# Motor.net
KiCad netlist of a schematic drawn in Altium Designer
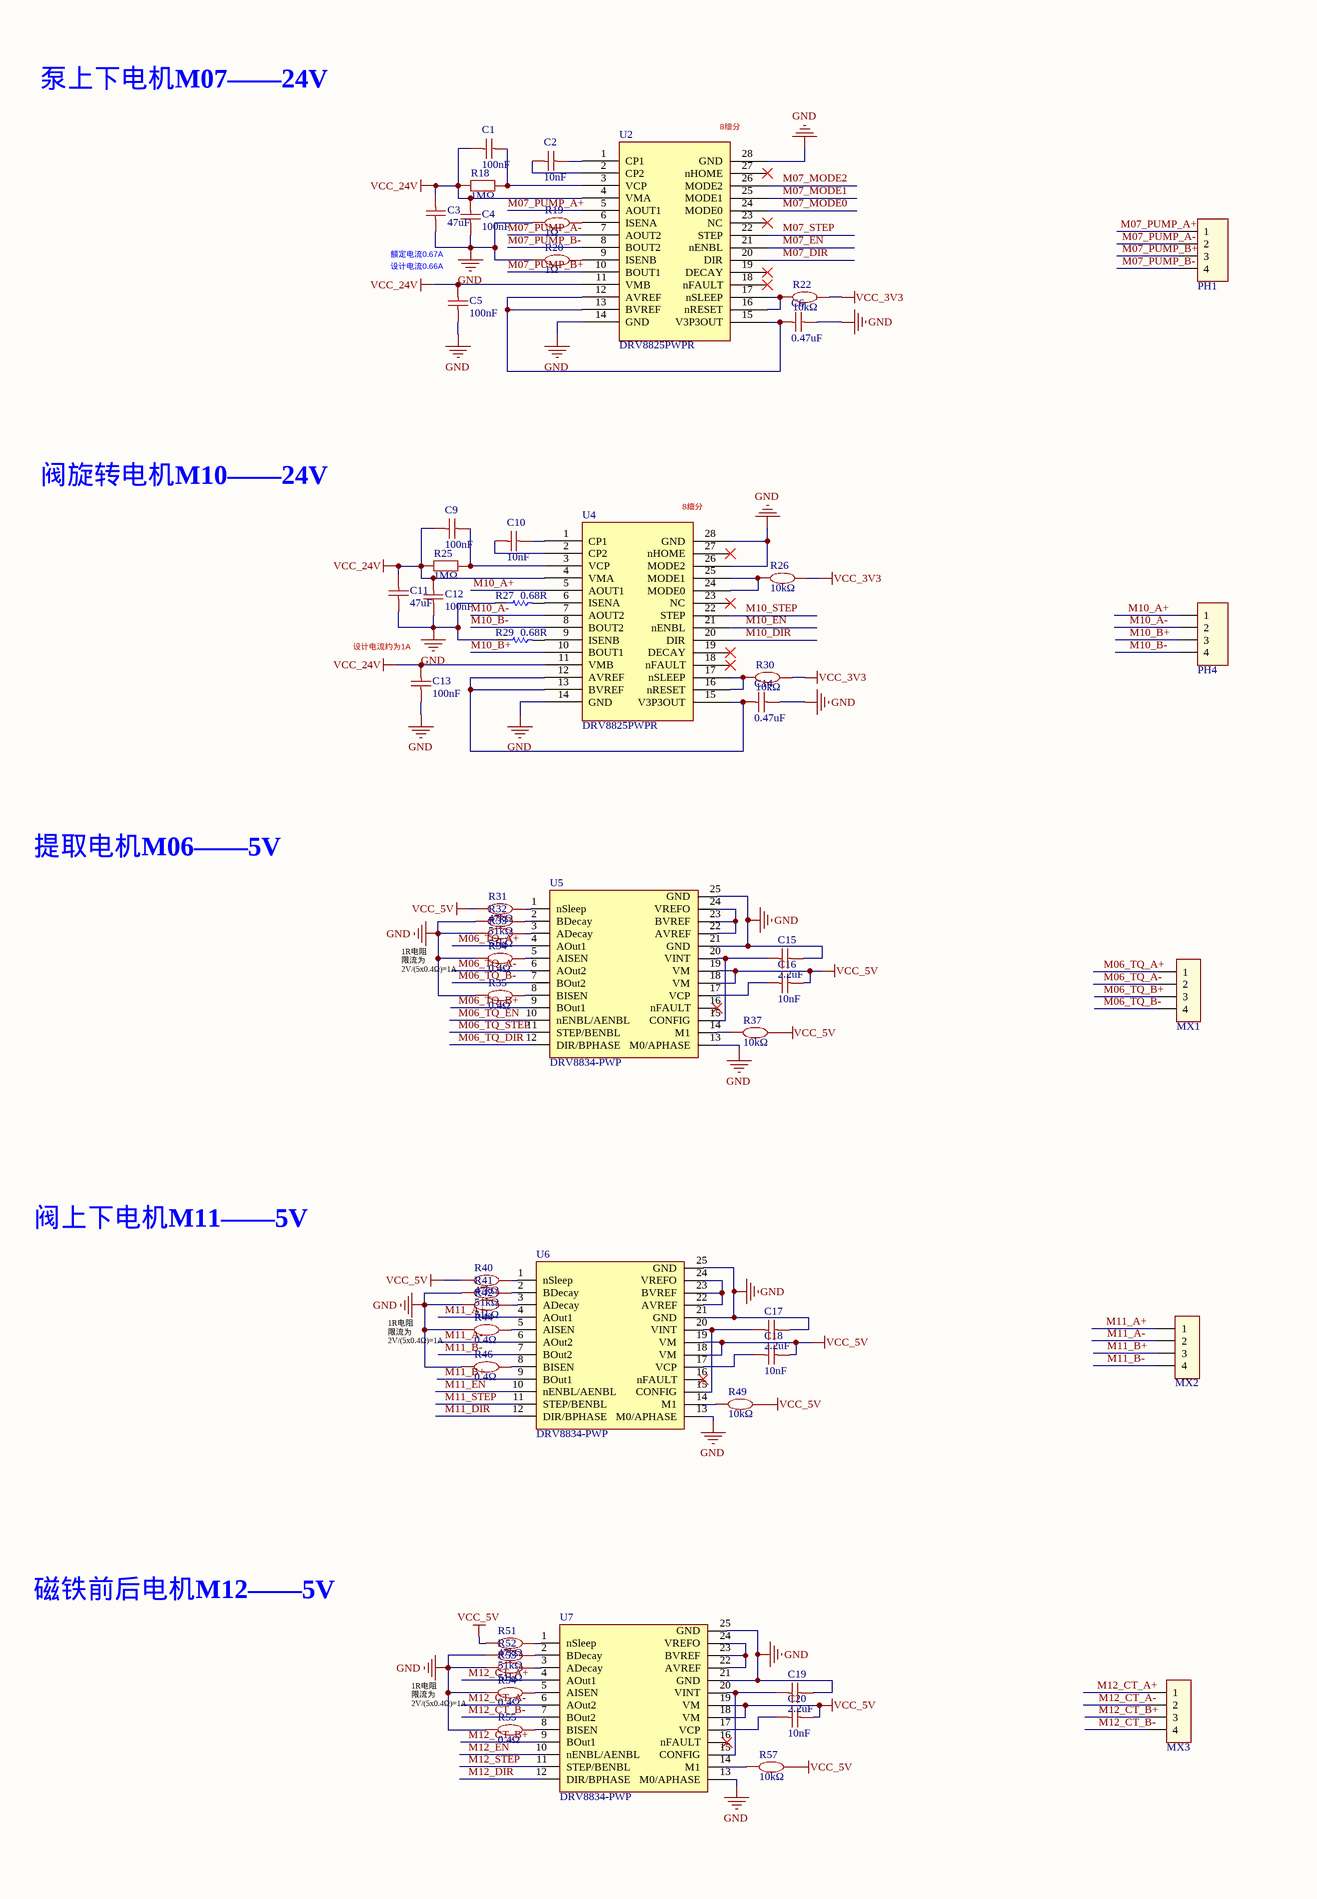
[diagram p0: Motor.SchDoc, left]
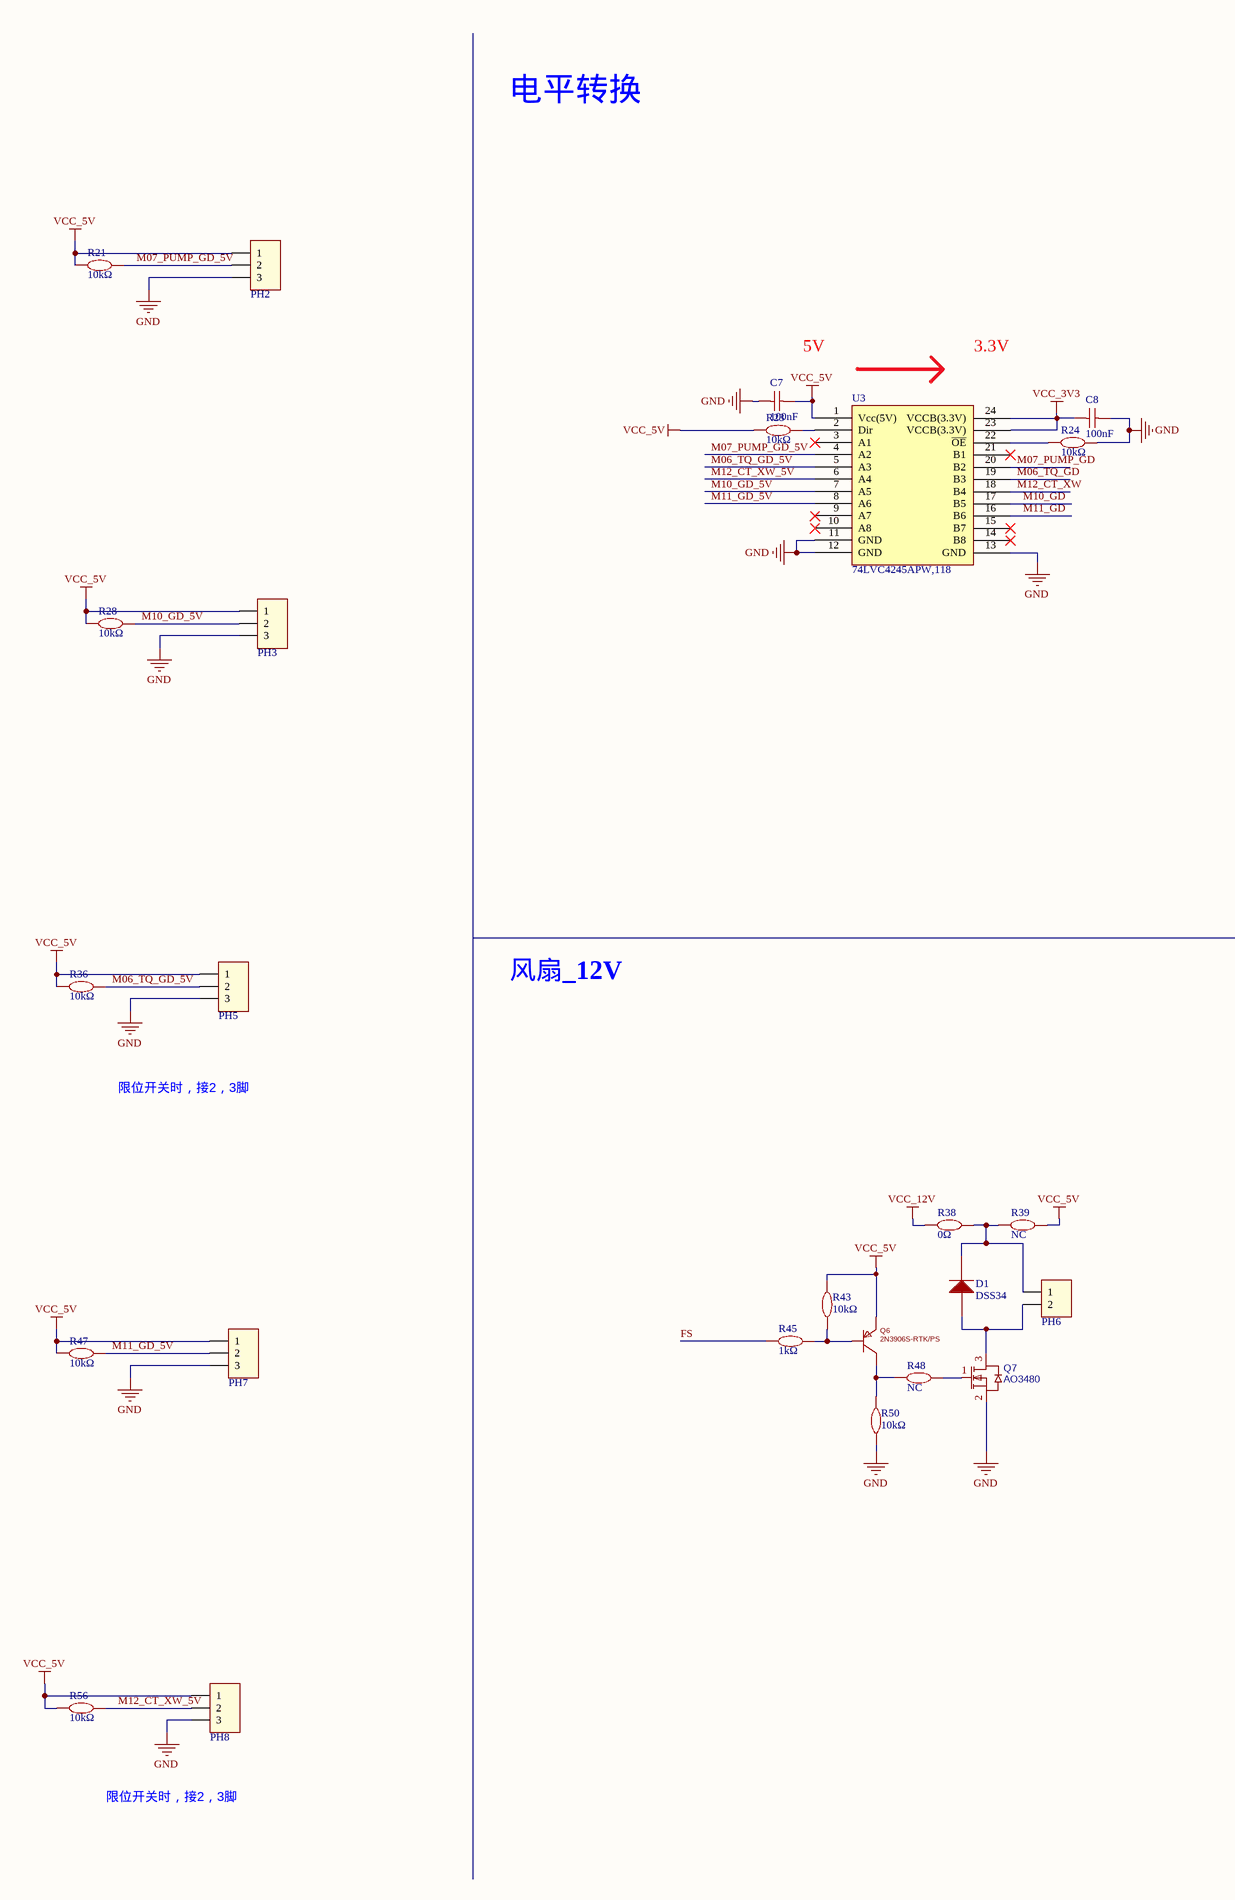
[diagram p1: Motor.SchDoc, right]

(export (version "E")
  (design (tool "Eeschema 10.0.6"))
  (components
    (comp (ref "C1")
      (value "100nF")
      (footprint "C0603")
      (description "贴片电容,X7R")
      (libsource (lib "XG_DW_POCT_2K10LED_3") (part "100nF/50V,C0603"))
    )
    (comp (ref "C2")
      (value "10nF")
      (footprint "C0603")
      (description "贴片电容,X7R")
      (libsource (lib "XG_DW_POCT_2K10LED_3") (part "10nF/50V,C0603"))
    )
    (comp (ref "C3")
      (value "47uF")
      (footprint "C1210")
      (description "贴片电容,X7R")
      (libsource (lib "XG_DW_POCT_2K10LED_3") (part "47uF/25V,C1210"))
    )
    (comp (ref "C4")
      (value "100nF")
      (footprint "C0603")
      (description "贴片电容,X7R")
      (libsource (lib "XG_DW_POCT_2K10LED_3") (part "100nF/50V,C0603"))
    )
    (comp (ref "C5")
      (value "100nF")
      (footprint "C0603")
      (description "贴片电容,X7R")
      (libsource (lib "XG_DW_POCT_2K10LED_3") (part "100nF/50V,C0603"))
    )
    (comp (ref "C6")
      (value "0.47uF")
      (footprint "C0603")
      (description "贴片电容,X7R")
      (libsource (lib "XG_DW_POCT_2K10LED_3") (part "0.47uF/50V,C0603"))
    )
    (comp (ref "C7")
      (value "100nF")
      (footprint "C0603")
      (description "贴片电容,X7R")
      (libsource (lib "XG_DW_POCT_2K10LED_3") (part "100nF/50V,C0603"))
    )
    (comp (ref "C8")
      (value "100nF")
      (footprint "C0603")
      (description "贴片电容,X7R")
      (libsource (lib "XG_DW_POCT_2K10LED_3") (part "100nF/50V,C0603"))
    )
    (comp (ref "C9")
      (value "100nF")
      (footprint "C0603")
      (description "贴片电容,X7R")
      (libsource (lib "XG_DW_POCT_2K10LED_3") (part "100nF/50V,C0603"))
    )
    (comp (ref "C10")
      (value "10nF")
      (footprint "C0603")
      (description "贴片电容,X7R")
      (libsource (lib "XG_DW_POCT_2K10LED_3") (part "10nF/50V,C0603"))
    )
    (comp (ref "C11")
      (value "47uF")
      (footprint "C1210")
      (description "贴片电容,X7R")
      (libsource (lib "XG_DW_POCT_2K10LED_3") (part "47uF/25V,C1210"))
    )
    (comp (ref "C12")
      (value "100nF")
      (footprint "C0603")
      (description "贴片电容,X7R")
      (libsource (lib "XG_DW_POCT_2K10LED_3") (part "100nF/50V,C0603"))
    )
    (comp (ref "C13")
      (value "100nF")
      (footprint "C0603")
      (description "贴片电容,X7R")
      (libsource (lib "XG_DW_POCT_2K10LED_3") (part "100nF/50V,C0603"))
    )
    (comp (ref "C14")
      (value "0.47uF")
      (footprint "C0603")
      (description "贴片电容,X7R")
      (libsource (lib "XG_DW_POCT_2K10LED_3") (part "0.47uF/50V,C0603"))
    )
    (comp (ref "C15")
      (value "2.2uF")
      (footprint "C0603")
      (description "贴片电容,X7R")
      (libsource (lib "XG_DW_POCT_2K10LED_3") (part "2.2uF/50V,C0603"))
    )
    (comp (ref "C16")
      (value "10nF")
      (footprint "C0603")
      (description "贴片电容,X7R")
      (libsource (lib "XG_DW_POCT_2K10LED_3") (part "10nF/50V,C0603"))
    )
    (comp (ref "C17")
      (value "2.2uF")
      (footprint "C0603")
      (description "贴片电容,X7R")
      (libsource (lib "XG_DW_POCT_2K10LED_3") (part "2.2uF/50V,C0603"))
    )
    (comp (ref "C18")
      (value "10nF")
      (footprint "C0603")
      (description "贴片电容,X7R")
      (libsource (lib "XG_DW_POCT_2K10LED_3") (part "10nF/50V,C0603"))
    )
    (comp (ref "C19")
      (value "2.2uF")
      (footprint "C0603")
      (description "贴片电容,X7R")
      (libsource (lib "XG_DW_POCT_2K10LED_3") (part "2.2uF/50V,C0603"))
    )
    (comp (ref "C20")
      (value "10nF")
      (footprint "C0603")
      (description "贴片电容,X7R")
      (libsource (lib "XG_DW_POCT_2K10LED_3") (part "10nF/50V,C0603"))
    )
    (comp (ref "D1")
      (value "DSS34")
      (footprint "SOD-123")
      (description "肖特基二极管")
      (libsource (lib "XG_DW_POCT_2K10LED_3") (part "DSS34,SOD-123"))
    )
    (comp (ref "MX1")
      (value "MX1.25-4P")
      (footprint "CONN-TH_4P-P1.25_HCTL_HC-1.25-4AW")
      (libsource (lib "XG_DW_POCT_2K10LED_3") (part "MX1.25-4P"))
    )
    (comp (ref "MX2")
      (value "MX1.25-4P")
      (footprint "CONN-TH_4P-P1.25_HCTL_HC-1.25-4AW")
      (libsource (lib "XG_DW_POCT_2K10LED_3") (part "MX1.25-4P"))
    )
    (comp (ref "MX3")
      (value "MX1.25-4P")
      (footprint "CONN-TH_4P-P1.25_HCTL_HC-1.25-4AW")
      (libsource (lib "XG_DW_POCT_2K10LED_3") (part "MX1.25-4P"))
    )
    (comp (ref "PH1")
      (value "PH2.0-4P")
      (footprint "PH2.0-4P 弯针")
      (libsource (lib "XG_DW_POCT_2K10LED_3") (part "PH2.0-4P"))
    )
    (comp (ref "PH2")
      (value "PH2.0-3P")
      (footprint "PH2.0-3P 弯针")
      (libsource (lib "XG_DW_POCT_2K10LED_3") (part "PH2.0-3P"))
    )
    (comp (ref "PH3")
      (value "PH2.0-3P")
      (footprint "PH2.0-3P 弯针")
      (libsource (lib "XG_DW_POCT_2K10LED_3") (part "PH2.0-3P"))
    )
    (comp (ref "PH4")
      (value "PH2.0-4P")
      (footprint "PH2.0-4P 弯针")
      (libsource (lib "XG_DW_POCT_2K10LED_3") (part "PH2.0-4P"))
    )
    (comp (ref "PH5")
      (value "PH2.0-3P")
      (footprint "PH2.0-3P 弯针")
      (libsource (lib "XG_DW_POCT_2K10LED_3") (part "PH2.0-3P"))
    )
    (comp (ref "PH6")
      (value "PH2.0-2P")
      (footprint "PH2.0-2P 弯针")
      (libsource (lib "XG_DW_POCT_2K10LED_3") (part "PH2.0-2P"))
    )
    (comp (ref "PH7")
      (value "PH2.0-3P")
      (footprint "PH2.0-3P 弯针")
      (libsource (lib "XG_DW_POCT_2K10LED_3") (part "PH2.0-3P"))
    )
    (comp (ref "PH8")
      (value "PH2.0-3P")
      (footprint "PH2.0-3P 弯针")
      (libsource (lib "XG_DW_POCT_2K10LED_3") (part "PH2.0-3P"))
    )
    (comp (ref "Q6")
      (value "2N3906S-RTK/PS")
      (footprint "SOT-23-3_L2.9-W1.3-P1.90-LS2.4-TR")
      (fields (field (name "MANUFACTURER") "KEC"))
      (libsource (lib "XG_DW_POCT_2K10LED_3") (part "2N3906S-RTK/PS"))
    )
    (comp (ref "Q7")
      (value "AO3480")
      (footprint "SOT-23(SOT-23-3)")
      (libsource (lib "XG_DW_POCT_2K10LED_3") (part "AO3480"))
    )
    (comp (ref "R18")
      (value "1MΩ")
      (footprint "R0603")
      (description "贴片电阻")
      (libsource (lib "XG_DW_POCT_2K10LED_3") (part "1MΩ,R0603"))
    )
    (comp (ref "R19")
      (value "1Ω")
      (footprint "R0603")
      (description "贴片电阻")
      (libsource (lib "XG_DW_POCT_2K10LED_3") (part "1Ω,R0603"))
    )
    (comp (ref "R20")
      (value "1Ω")
      (footprint "R0603")
      (description "贴片电阻")
      (libsource (lib "XG_DW_POCT_2K10LED_3") (part "1Ω,R0603"))
    )
    (comp (ref "R21")
      (value "10kΩ")
      (footprint "R0603")
      (description "电阻类型:厚膜电阻;阻值:10kΩ;精度:±1%;功率:100mW;最大工作电压:75V;温度系数:±100ppm/℃;")
      (libsource (lib "XG_DW_POCT_2K10LED_3") (part "10kΩ,R0603"))
    )
    (comp (ref "R22")
      (value "10kΩ")
      (footprint "R0603")
      (description "电阻类型:厚膜电阻;阻值:10kΩ;精度:±1%;功率:100mW;最大工作电压:75V;温度系数:±100ppm/℃;")
      (libsource (lib "XG_DW_POCT_2K10LED_3") (part "10kΩ,R0603"))
    )
    (comp (ref "R23")
      (value "10kΩ")
      (footprint "R0603")
      (description "电阻类型:厚膜电阻;阻值:10kΩ;精度:±1%;功率:100mW;最大工作电压:75V;温度系数:±100ppm/℃;")
      (libsource (lib "XG_DW_POCT_2K10LED_3") (part "10kΩ,R0603"))
    )
    (comp (ref "R24")
      (value "10kΩ")
      (footprint "R0603")
      (description "电阻类型:厚膜电阻;阻值:10kΩ;精度:±1%;功率:100mW;最大工作电压:75V;温度系数:±100ppm/℃;")
      (libsource (lib "XG_DW_POCT_2K10LED_3") (part "10kΩ,R0603"))
    )
    (comp (ref "R25")
      (value "1MΩ")
      (footprint "R0603")
      (description "贴片电阻")
      (libsource (lib "XG_DW_POCT_2K10LED_3") (part "1MΩ,R0603"))
    )
    (comp (ref "R26")
      (value "10kΩ")
      (footprint "R0603")
      (description "电阻类型:厚膜电阻;阻值:10kΩ;精度:±1%;功率:100mW;最大工作电压:75V;温度系数:±100ppm/℃;")
      (libsource (lib "XG_DW_POCT_2K10LED_3") (part "10kΩ,R0603"))
    )
    (comp (ref "R27")
      (value "0.68R")
      (footprint "R0603")
      (description "Resistor")
      (fields (field (name "PUBLISHER") "Altium Limited"))
      (libsource (lib "czb") (part "Res"))
    )
    (comp (ref "R28")
      (value "10kΩ")
      (footprint "R0603")
      (description "电阻类型:厚膜电阻;阻值:10kΩ;精度:±1%;功率:100mW;最大工作电压:75V;温度系数:±100ppm/℃;")
      (libsource (lib "XG_DW_POCT_2K10LED_3") (part "10kΩ,R0603"))
    )
    (comp (ref "R29")
      (value "0.68R")
      (footprint "R0603")
      (description "Resistor")
      (fields (field (name "PUBLISHER") "Altium Limited"))
      (libsource (lib "czb") (part "Res"))
    )
    (comp (ref "R30")
      (value "10kΩ")
      (footprint "R0603")
      (description "电阻类型:厚膜电阻;阻值:10kΩ;精度:±1%;功率:100mW;最大工作电压:75V;温度系数:±100ppm/℃;")
      (libsource (lib "XG_DW_POCT_2K10LED_3") (part "10kΩ,R0603"))
    )
    (comp (ref "R31")
      (value "47kΩ")
      (footprint "R0603")
      (description "贴片电阻")
      (libsource (lib "XG_DW_POCT_2K10LED_3") (part "47kΩ,R0603"))
    )
    (comp (ref "R32")
      (value "51kΩ")
      (footprint "R0603")
      (description "电阻类型:厚膜电阻;阻值:51kΩ;精度:±1%;功率:100mW;最大工作电压:75V;温度系数:±100ppm/℃;")
      (libsource (lib "XG_DW_POCT_2K10LED_3") (part "51kΩ,R0603"))
    )
    (comp (ref "R33")
      (value "51kΩ")
      (footprint "R0603")
      (description "电阻类型:厚膜电阻;阻值:51kΩ;精度:±1%;功率:100mW;最大工作电压:75V;温度系数:±100ppm/℃;")
      (libsource (lib "XG_DW_POCT_2K10LED_3") (part "51kΩ,R0603"))
    )
    (comp (ref "R34")
      (value "0.4Ω")
      (footprint "R0603")
      (description "贴片电阻")
      (libsource (lib "XG_DW_POCT_2K10LED_3") (part "0.4Ω,R0603"))
    )
    (comp (ref "R35")
      (value "0.4Ω")
      (footprint "R0603")
      (description "贴片电阻")
      (libsource (lib "XG_DW_POCT_2K10LED_3") (part "0.4Ω,R0603"))
    )
    (comp (ref "R36")
      (value "10kΩ")
      (footprint "R0603")
      (description "电阻类型:厚膜电阻;阻值:10kΩ;精度:±1%;功率:100mW;最大工作电压:75V;温度系数:±100ppm/℃;")
      (libsource (lib "XG_DW_POCT_2K10LED_3") (part "10kΩ,R0603"))
    )
    (comp (ref "R37")
      (value "10kΩ")
      (footprint "R0603")
      (description "电阻类型:厚膜电阻;阻值:10kΩ;精度:±1%;功率:100mW;最大工作电压:75V;温度系数:±100ppm/℃;")
      (libsource (lib "XG_DW_POCT_2K10LED_3") (part "10kΩ,R0603"))
    )
    (comp (ref "R38")
      (value "0Ω")
      (footprint "R0603")
      (description "贴片电阻")
      (libsource (lib "XG_DW_POCT_2K10LED_3") (part "0Ω,R0603"))
    )
    (comp (ref "R39")
      (value "NC")
      (footprint "R0603")
      (libsource (lib "XG_DW_POCT_2K10LED_3") (part "NC,R0603"))
    )
    (comp (ref "R40")
      (value "47kΩ")
      (footprint "R0603")
      (description "贴片电阻")
      (libsource (lib "XG_DW_POCT_2K10LED_3") (part "47kΩ,R0603"))
    )
    (comp (ref "R41")
      (value "51kΩ")
      (footprint "R0603")
      (description "电阻类型:厚膜电阻;阻值:51kΩ;精度:±1%;功率:100mW;最大工作电压:75V;温度系数:±100ppm/℃;")
      (libsource (lib "XG_DW_POCT_2K10LED_3") (part "51kΩ,R0603"))
    )
    (comp (ref "R42")
      (value "51kΩ")
      (footprint "R0603")
      (description "电阻类型:厚膜电阻;阻值:51kΩ;精度:±1%;功率:100mW;最大工作电压:75V;温度系数:±100ppm/℃;")
      (libsource (lib "XG_DW_POCT_2K10LED_3") (part "51kΩ,R0603"))
    )
    (comp (ref "R43")
      (value "10kΩ")
      (footprint "R0603")
      (description "电阻类型:厚膜电阻;阻值:10kΩ;精度:±1%;功率:100mW;最大工作电压:75V;温度系数:±100ppm/℃;")
      (libsource (lib "XG_DW_POCT_2K10LED_3") (part "10kΩ,R0603"))
    )
    (comp (ref "R44")
      (value "0.4Ω")
      (footprint "R0603")
      (description "贴片电阻")
      (libsource (lib "XG_DW_POCT_2K10LED_3") (part "0.4Ω,R0603"))
    )
    (comp (ref "R45")
      (value "1kΩ")
      (footprint "R0603")
      (description "电阻类型:厚膜电阻;阻值:1kΩ;精度:±1%;功率:125mW;最大工作电压:150V;温度系数:±100ppm/℃;")
      (libsource (lib "XG_DW_POCT_2K10LED_3") (part "1kΩ,R0603"))
    )
    (comp (ref "R46")
      (value "0.4Ω")
      (footprint "R0603")
      (description "贴片电阻")
      (libsource (lib "XG_DW_POCT_2K10LED_3") (part "0.4Ω,R0603"))
    )
    (comp (ref "R47")
      (value "10kΩ")
      (footprint "R0603")
      (description "电阻类型:厚膜电阻;阻值:10kΩ;精度:±1%;功率:100mW;最大工作电压:75V;温度系数:±100ppm/℃;")
      (libsource (lib "XG_DW_POCT_2K10LED_3") (part "10kΩ,R0603"))
    )
    (comp (ref "R48")
      (value "NC")
      (footprint "R0603")
      (libsource (lib "XG_DW_POCT_2K10LED_3") (part "NC,R0603"))
    )
    (comp (ref "R49")
      (value "10kΩ")
      (footprint "R0603")
      (description "电阻类型:厚膜电阻;阻值:10kΩ;精度:±1%;功率:100mW;最大工作电压:75V;温度系数:±100ppm/℃;")
      (libsource (lib "XG_DW_POCT_2K10LED_3") (part "10kΩ,R0603"))
    )
    (comp (ref "R50")
      (value "10kΩ")
      (footprint "R0603")
      (description "电阻类型:厚膜电阻;阻值:10kΩ;精度:±1%;功率:100mW;最大工作电压:75V;温度系数:±100ppm/℃;")
      (libsource (lib "XG_DW_POCT_2K10LED_3") (part "10kΩ,R0603"))
    )
    (comp (ref "R51")
      (value "47kΩ")
      (footprint "R0603")
      (description "贴片电阻")
      (libsource (lib "XG_DW_POCT_2K10LED_3") (part "47kΩ,R0603"))
    )
    (comp (ref "R52")
      (value "51kΩ")
      (footprint "R0603")
      (description "电阻类型:厚膜电阻;阻值:51kΩ;精度:±1%;功率:100mW;最大工作电压:75V;温度系数:±100ppm/℃;")
      (libsource (lib "XG_DW_POCT_2K10LED_3") (part "51kΩ,R0603"))
    )
    (comp (ref "R53")
      (value "51kΩ")
      (footprint "R0603")
      (description "电阻类型:厚膜电阻;阻值:51kΩ;精度:±1%;功率:100mW;最大工作电压:75V;温度系数:±100ppm/℃;")
      (libsource (lib "XG_DW_POCT_2K10LED_3") (part "51kΩ,R0603"))
    )
    (comp (ref "R54")
      (value "0.4Ω")
      (footprint "R0603")
      (description "贴片电阻")
      (libsource (lib "XG_DW_POCT_2K10LED_3") (part "0.4Ω,R0603"))
    )
    (comp (ref "R55")
      (value "0.4Ω")
      (footprint "R0603")
      (description "贴片电阻")
      (libsource (lib "XG_DW_POCT_2K10LED_3") (part "0.4Ω,R0603"))
    )
    (comp (ref "R56")
      (value "10kΩ")
      (footprint "R0603")
      (description "电阻类型:厚膜电阻;阻值:10kΩ;精度:±1%;功率:100mW;最大工作电压:75V;温度系数:±100ppm/℃;")
      (libsource (lib "XG_DW_POCT_2K10LED_3") (part "10kΩ,R0603"))
    )
    (comp (ref "R57")
      (value "10kΩ")
      (footprint "R0603")
      (description "电阻类型:厚膜电阻;阻值:10kΩ;精度:±1%;功率:100mW;最大工作电压:75V;温度系数:±100ppm/℃;")
      (libsource (lib "XG_DW_POCT_2K10LED_3") (part "10kΩ,R0603"))
    )
    (comp (ref "U2")
      (value "DRV8825PWPR")
      (footprint "HTSSOP-28")
      (libsource (lib "XG_DW_POCT_2K10LED_3") (part "DRV8825PWPR"))
    )
    (comp (ref "U3")
      (value "74LVC4245APW,118")
      (footprint "TSSOP-24")
      (description "转换器/电平移位器；通道类型 双向；工作电压(VCCA) 1.5V~5.5V；工作电压(VCCB) 1.5V~3.6V； 通道数 1；\r\n每个电路通道数 8；输出类型 三态")
      (libsource (lib "XG_DW_POCT_2K10LED_3") (part "74LVC4245APW"))
    )
    (comp (ref "U4")
      (value "DRV8825PWPR")
      (footprint "HTSSOP-28")
      (libsource (lib "XG_DW_POCT_2K10LED_3") (part "DRV8825PWPR"))
    )
    (comp (ref "U5")
      (value "DRV8834-PWP")
      (footprint "HTSSOP-24")
      (libsource (lib "XG_DW_POCT_2K10LED_3") (part "DRV8834-PWP"))
    )
    (comp (ref "U6")
      (value "DRV8834-PWP")
      (footprint "HTSSOP-24")
      (libsource (lib "XG_DW_POCT_2K10LED_3") (part "DRV8834-PWP"))
    )
    (comp (ref "U7")
      (value "DRV8834-PWP")
      (footprint "HTSSOP-24")
      (libsource (lib "XG_DW_POCT_2K10LED_3") (part "DRV8834-PWP"))
    )
  )
  (nets
    (net (code "1") (name "/FS") (class "Default")
      (node (ref "R45") (pin "2") (pinfunction "2_2") (pintype "passive"))
    )
    (net (code "2") (name "/M06_TQ_A+") (class "Default")
      (node (ref "MX1") (pin "1") (pinfunction "1_1") (pintype "passive"))
      (node (ref "U5") (pin "4") (pinfunction "AOut1_4") (pintype "passive"))
    )
    (net (code "3") (name "/M06_TQ_A-") (class "Default")
      (node (ref "MX1") (pin "2") (pinfunction "2_2") (pintype "passive"))
      (node (ref "U5") (pin "6") (pinfunction "AOut2_6") (pintype "passive"))
    )
    (net (code "4") (name "/M06_TQ_B+") (class "Default")
      (node (ref "MX1") (pin "3") (pinfunction "3_3") (pintype "passive"))
      (node (ref "U5") (pin "9") (pinfunction "BOut1_9") (pintype "passive"))
    )
    (net (code "5") (name "/M06_TQ_B-") (class "Default")
      (node (ref "MX1") (pin "4") (pinfunction "4_4") (pintype "passive"))
      (node (ref "U5") (pin "7") (pinfunction "BOut2_7") (pintype "passive"))
    )
    (net (code "6") (name "/M06_TQ_DIR") (class "Default")
      (node (ref "U5") (pin "12") (pinfunction "DIR/BPHASE_12") (pintype "passive"))
    )
    (net (code "7") (name "/M06_TQ_EN") (class "Default")
      (node (ref "U5") (pin "10") (pinfunction "nENBL/AENBL_10") (pintype "passive"))
    )
    (net (code "8") (name "/M06_TQ_GD") (class "Default")
      (node (ref "U3") (pin "19") (pinfunction "B3_19") (pintype "passive"))
    )
    (net (code "9") (name "/M06_TQ_GD_5V") (class "Default")
      (node (ref "PH5") (pin "2") (pinfunction "2_2") (pintype "passive"))
      (node (ref "R36") (pin "1") (pinfunction "1_1") (pintype "passive"))
      (node (ref "U3") (pin "5") (pinfunction "A3_5") (pintype "passive"))
    )
    (net (code "10") (name "/M06_TQ_STEP") (class "Default")
      (node (ref "U5") (pin "11") (pinfunction "STEP/BENBL_11") (pintype "passive"))
    )
    (net (code "11") (name "/M07_DIR") (class "Default")
      (node (ref "U2") (pin "20") (pinfunction "DIR_20") (pintype "passive"))
    )
    (net (code "12") (name "/M07_EN") (class "Default")
      (node (ref "U2") (pin "21") (pinfunction "nENBL_21") (pintype "passive"))
    )
    (net (code "13") (name "/M07_MODE0") (class "Default")
      (node (ref "U2") (pin "24") (pinfunction "MODE0_24") (pintype "passive"))
    )
    (net (code "14") (name "/M07_MODE1") (class "Default")
      (node (ref "U2") (pin "25") (pinfunction "MODE1_25") (pintype "passive"))
    )
    (net (code "15") (name "/M07_MODE2") (class "Default")
      (node (ref "U2") (pin "26") (pinfunction "MODE2_26") (pintype "passive"))
    )
    (net (code "16") (name "/M07_PUMP_A+") (class "Default")
      (node (ref "PH1") (pin "1") (pinfunction "1_1") (pintype "passive"))
      (node (ref "U2") (pin "5") (pinfunction "AOUT1_5") (pintype "passive"))
    )
    (net (code "17") (name "/M07_PUMP_A-") (class "Default")
      (node (ref "PH1") (pin "2") (pinfunction "2_2") (pintype "passive"))
      (node (ref "U2") (pin "7") (pinfunction "AOUT2_7") (pintype "passive"))
    )
    (net (code "18") (name "/M07_PUMP_B+") (class "Default")
      (node (ref "PH1") (pin "3") (pinfunction "3_3") (pintype "passive"))
      (node (ref "U2") (pin "10") (pinfunction "BOUT1_10") (pintype "passive"))
    )
    (net (code "19") (name "/M07_PUMP_B-") (class "Default")
      (node (ref "PH1") (pin "4") (pinfunction "4_4") (pintype "passive"))
      (node (ref "U2") (pin "8") (pinfunction "BOUT2_8") (pintype "passive"))
    )
    (net (code "20") (name "/M07_PUMP_GD") (class "Default")
      (node (ref "U3") (pin "20") (pinfunction "B2_20") (pintype "passive"))
    )
    (net (code "21") (name "/M07_PUMP_GD_5V") (class "Default")
      (node (ref "PH2") (pin "2") (pinfunction "2_2") (pintype "passive"))
      (node (ref "R21") (pin "1") (pinfunction "1_1") (pintype "passive"))
      (node (ref "U3") (pin "4") (pinfunction "A2_4") (pintype "passive"))
    )
    (net (code "22") (name "/M07_STEP") (class "Default")
      (node (ref "U2") (pin "22") (pinfunction "STEP_22") (pintype "passive"))
    )
    (net (code "23") (name "/M10_A+") (class "Default")
      (node (ref "PH4") (pin "1") (pinfunction "1_1") (pintype "passive"))
      (node (ref "U4") (pin "5") (pinfunction "AOUT1_5") (pintype "passive"))
    )
    (net (code "24") (name "/M10_A-") (class "Default")
      (node (ref "PH4") (pin "2") (pinfunction "2_2") (pintype "passive"))
      (node (ref "U4") (pin "7") (pinfunction "AOUT2_7") (pintype "passive"))
    )
    (net (code "25") (name "/M10_B+") (class "Default")
      (node (ref "PH4") (pin "3") (pinfunction "3_3") (pintype "passive"))
      (node (ref "U4") (pin "10") (pinfunction "BOUT1_10") (pintype "passive"))
    )
    (net (code "26") (name "/M10_B-") (class "Default")
      (node (ref "PH4") (pin "4") (pinfunction "4_4") (pintype "passive"))
      (node (ref "U4") (pin "8") (pinfunction "BOUT2_8") (pintype "passive"))
    )
    (net (code "27") (name "/M10_DIR") (class "Default")
      (node (ref "U4") (pin "20") (pinfunction "DIR_20") (pintype "passive"))
    )
    (net (code "28") (name "/M10_EN") (class "Default")
      (node (ref "U4") (pin "21") (pinfunction "nENBL_21") (pintype "passive"))
    )
    (net (code "29") (name "/M10_GD") (class "Default")
      (node (ref "U3") (pin "17") (pinfunction "B5_17") (pintype "passive"))
    )
    (net (code "30") (name "/M10_GD_5V") (class "Default")
      (node (ref "PH3") (pin "2") (pinfunction "2_2") (pintype "passive"))
      (node (ref "R28") (pin "1") (pinfunction "1_1") (pintype "passive"))
      (node (ref "U3") (pin "7") (pinfunction "A5_7") (pintype "passive"))
    )
    (net (code "31") (name "/M10_STEP") (class "Default")
      (node (ref "U4") (pin "22") (pinfunction "STEP_22") (pintype "passive"))
    )
    (net (code "32") (name "/M11_A+") (class "Default")
      (node (ref "MX2") (pin "1") (pinfunction "1_1") (pintype "passive"))
      (node (ref "U6") (pin "4") (pinfunction "AOut1_4") (pintype "passive"))
    )
    (net (code "33") (name "/M11_A-") (class "Default")
      (node (ref "MX2") (pin "2") (pinfunction "2_2") (pintype "passive"))
      (node (ref "U6") (pin "6") (pinfunction "AOut2_6") (pintype "passive"))
    )
    (net (code "34") (name "/M11_B+") (class "Default")
      (node (ref "MX2") (pin "3") (pinfunction "3_3") (pintype "passive"))
      (node (ref "U6") (pin "9") (pinfunction "BOut1_9") (pintype "passive"))
    )
    (net (code "35") (name "/M11_B-") (class "Default")
      (node (ref "MX2") (pin "4") (pinfunction "4_4") (pintype "passive"))
      (node (ref "U6") (pin "7") (pinfunction "BOut2_7") (pintype "passive"))
    )
    (net (code "36") (name "/M11_DIR") (class "Default")
      (node (ref "U6") (pin "12") (pinfunction "DIR/BPHASE_12") (pintype "passive"))
    )
    (net (code "37") (name "/M11_EN") (class "Default")
      (node (ref "U6") (pin "10") (pinfunction "nENBL/AENBL_10") (pintype "passive"))
    )
    (net (code "38") (name "/M11_GD") (class "Default")
      (node (ref "U3") (pin "16") (pinfunction "B6_16") (pintype "passive"))
    )
    (net (code "39") (name "/M11_GD_5V") (class "Default")
      (node (ref "PH7") (pin "2") (pinfunction "2_2") (pintype "passive"))
      (node (ref "R47") (pin "1") (pinfunction "1_1") (pintype "passive"))
      (node (ref "U3") (pin "8") (pinfunction "A6_8") (pintype "passive"))
    )
    (net (code "40") (name "/M11_STEP") (class "Default")
      (node (ref "U6") (pin "11") (pinfunction "STEP/BENBL_11") (pintype "passive"))
    )
    (net (code "41") (name "/M12_CT_A+") (class "Default")
      (node (ref "MX3") (pin "1") (pinfunction "1_1") (pintype "passive"))
      (node (ref "U7") (pin "4") (pinfunction "AOut1_4") (pintype "passive"))
    )
    (net (code "42") (name "/M12_CT_A-") (class "Default")
      (node (ref "MX3") (pin "2") (pinfunction "2_2") (pintype "passive"))
      (node (ref "U7") (pin "6") (pinfunction "AOut2_6") (pintype "passive"))
    )
    (net (code "43") (name "/M12_CT_B+") (class "Default")
      (node (ref "MX3") (pin "3") (pinfunction "3_3") (pintype "passive"))
      (node (ref "U7") (pin "9") (pinfunction "BOut1_9") (pintype "passive"))
    )
    (net (code "44") (name "/M12_CT_B-") (class "Default")
      (node (ref "MX3") (pin "4") (pinfunction "4_4") (pintype "passive"))
      (node (ref "U7") (pin "7") (pinfunction "BOut2_7") (pintype "passive"))
    )
    (net (code "45") (name "/M12_CT_XW") (class "Default")
      (node (ref "U3") (pin "18") (pinfunction "B4_18") (pintype "passive"))
    )
    (net (code "46") (name "/M12_CT_XW_5V") (class "Default")
      (node (ref "PH8") (pin "2") (pinfunction "2_2") (pintype "passive"))
      (node (ref "R56") (pin "2") (pinfunction "2_2") (pintype "passive"))
      (node (ref "U3") (pin "6") (pinfunction "A4_6") (pintype "passive"))
    )
    (net (code "47") (name "/M12_DIR") (class "Default")
      (node (ref "U7") (pin "12") (pinfunction "DIR/BPHASE_12") (pintype "passive"))
    )
    (net (code "48") (name "/M12_EN") (class "Default")
      (node (ref "U7") (pin "10") (pinfunction "nENBL/AENBL_10") (pintype "passive"))
    )
    (net (code "49") (name "/M12_STEP") (class "Default")
      (node (ref "U7") (pin "11") (pinfunction "STEP/BENBL_11") (pintype "passive"))
    )
    (net (code "50") (name "GND") (class "Default")
      (node (ref "C11") (pin "1") (pinfunction "1_1") (pintype "passive"))
      (node (ref "C12") (pin "1") (pinfunction "1_1") (pintype "passive"))
      (node (ref "C13") (pin "1") (pinfunction "1_1") (pintype "passive"))
      (node (ref "C14") (pin "2") (pinfunction "2_2") (pintype "passive"))
      (node (ref "C15") (pin "1") (pinfunction "1_1") (pintype "passive"))
      (node (ref "C17") (pin "1") (pinfunction "1_1") (pintype "passive"))
      (node (ref "C19") (pin "1") (pinfunction "1_1") (pintype "passive"))
      (node (ref "C3") (pin "1") (pinfunction "1_1") (pintype "passive"))
      (node (ref "C4") (pin "1") (pinfunction "1_1") (pintype "passive"))
      (node (ref "C5") (pin "1") (pinfunction "1_1") (pintype "passive"))
      (node (ref "C6") (pin "2") (pinfunction "2_2") (pintype "passive"))
      (node (ref "C7") (pin "1") (pinfunction "1_1") (pintype "passive"))
      (node (ref "C8") (pin "2") (pinfunction "2_2") (pintype "passive"))
      (node (ref "PH2") (pin "3") (pinfunction "3_3") (pintype "passive"))
      (node (ref "PH3") (pin "3") (pinfunction "3_3") (pintype "passive"))
      (node (ref "PH5") (pin "3") (pinfunction "3_3") (pintype "passive"))
      (node (ref "PH7") (pin "3") (pinfunction "3_3") (pintype "passive"))
      (node (ref "PH8") (pin "3") (pinfunction "3_3") (pintype "passive"))
      (node (ref "Q7") (pin "2") (pinfunction "S_2") (pintype "passive"))
      (node (ref "R19") (pin "1") (pinfunction "1_1") (pintype "passive"))
      (node (ref "R20") (pin "1") (pinfunction "1_1") (pintype "passive"))
      (node (ref "R24") (pin "1") (pinfunction "1_1") (pintype "passive"))
      (node (ref "R27") (pin "1") (pinfunction "1_1") (pintype "passive"))
      (node (ref "R29") (pin "1") (pinfunction "1_1") (pintype "passive"))
      (node (ref "R32") (pin "2") (pinfunction "2_2") (pintype "passive"))
      (node (ref "R33") (pin "2") (pinfunction "2_2") (pintype "passive"))
      (node (ref "R34") (pin "2") (pinfunction "2_2") (pintype "passive"))
      (node (ref "R35") (pin "2") (pinfunction "2_2") (pintype "passive"))
      (node (ref "R41") (pin "2") (pinfunction "2_2") (pintype "passive"))
      (node (ref "R42") (pin "2") (pinfunction "2_2") (pintype "passive"))
      (node (ref "R44") (pin "2") (pinfunction "2_2") (pintype "passive"))
      (node (ref "R46") (pin "2") (pinfunction "2_2") (pintype "passive"))
      (node (ref "R50") (pin "1") (pinfunction "1_1") (pintype "passive"))
      (node (ref "R52") (pin "2") (pinfunction "2_2") (pintype "passive"))
      (node (ref "R53") (pin "2") (pinfunction "2_2") (pintype "passive"))
      (node (ref "R54") (pin "2") (pinfunction "2_2") (pintype "passive"))
      (node (ref "R55") (pin "2") (pinfunction "2_2") (pintype "passive"))
      (node (ref "U2") (pin "14") (pinfunction "GND_14") (pintype "passive"))
      (node (ref "U2") (pin "28") (pinfunction "GND_28") (pintype "passive"))
      (node (ref "U3") (pin "11") (pinfunction "GND_11") (pintype "passive"))
      (node (ref "U3") (pin "12") (pinfunction "GND_12") (pintype "passive"))
      (node (ref "U3") (pin "13") (pinfunction "GND_13") (pintype "passive"))
      (node (ref "U4") (pin "14") (pinfunction "GND_14") (pintype "passive"))
      (node (ref "U4") (pin "26") (pinfunction "MODE2_26") (pintype "passive"))
      (node (ref "U4") (pin "28") (pinfunction "GND_28") (pintype "passive"))
      (node (ref "U5") (pin "13") (pinfunction "M0/APHASE_13") (pintype "passive"))
      (node (ref "U5") (pin "21") (pinfunction "GND_21") (pintype "passive"))
      (node (ref "U5") (pin "25") (pinfunction "GND_25") (pintype "passive"))
      (node (ref "U6") (pin "13") (pinfunction "M0/APHASE_13") (pintype "passive"))
      (node (ref "U6") (pin "21") (pinfunction "GND_21") (pintype "passive"))
      (node (ref "U6") (pin "25") (pinfunction "GND_25") (pintype "passive"))
      (node (ref "U7") (pin "13") (pinfunction "M0/APHASE_13") (pintype "passive"))
      (node (ref "U7") (pin "21") (pinfunction "GND_21") (pintype "passive"))
      (node (ref "U7") (pin "25") (pinfunction "GND_25") (pintype "passive"))
    )
    (net (code "51") (name "Net-(D1-A)") (class "Default")
      (node (ref "D1") (pin "1") (pinfunction "A_1") (pintype "passive"))
      (node (ref "PH6") (pin "2") (pinfunction "2_2") (pintype "passive"))
      (node (ref "Q7") (pin "3") (pinfunction "D_3") (pintype "passive"))
    )
    (net (code "52") (name "Net-(D1-K)") (class "Default")
      (node (ref "D1") (pin "2") (pinfunction "K_2") (pintype "passive"))
      (node (ref "PH6") (pin "1") (pinfunction "1_1") (pintype "passive"))
      (node (ref "R38") (pin "2") (pinfunction "2_2") (pintype "passive"))
      (node (ref "R39") (pin "1") (pinfunction "1_1") (pintype "passive"))
    )
    (net (code "53") (name "Net-(Q6-B)") (class "Default")
      (node (ref "Q6") (pin "2") (pinfunction "B_2") (pintype "passive"))
      (node (ref "R43") (pin "1") (pinfunction "1_1") (pintype "passive"))
      (node (ref "R45") (pin "1") (pinfunction "1_1") (pintype "passive"))
    )
    (net (code "54") (name "Net-(Q6-C)") (class "Default")
      (node (ref "Q6") (pin "3") (pinfunction "C_3") (pintype "passive"))
      (node (ref "R48") (pin "1") (pinfunction "1_1") (pintype "passive"))
      (node (ref "R50") (pin "2") (pinfunction "2_2") (pintype "passive"))
    )
    (net (code "55") (name "Net-(Q7-G)") (class "Default")
      (node (ref "Q7") (pin "1") (pinfunction "G_1") (pintype "passive"))
      (node (ref "R48") (pin "2") (pinfunction "2_2") (pintype "passive"))
    )
    (net (code "56") (name "Net-(U2-AVREF)") (class "Default")
      (node (ref "C6") (pin "1") (pinfunction "1_1") (pintype "passive"))
      (node (ref "U2") (pin "12") (pinfunction "AVREF_12") (pintype "passive"))
      (node (ref "U2") (pin "13") (pinfunction "BVREF_13") (pintype "passive"))
      (node (ref "U2") (pin "15") (pinfunction "V3P3OUT_15") (pintype "passive"))
    )
    (net (code "57") (name "Net-(U2-CP1)") (class "Default")
      (node (ref "C2") (pin "2") (pinfunction "2_2") (pintype "passive"))
      (node (ref "U2") (pin "1") (pinfunction "CP1_1") (pintype "passive"))
    )
    (net (code "58") (name "Net-(U2-CP2)") (class "Default")
      (node (ref "C2") (pin "1") (pinfunction "1_1") (pintype "passive"))
      (node (ref "U2") (pin "2") (pinfunction "CP2_2") (pintype "passive"))
    )
    (net (code "59") (name "Net-(U2-ISENA)") (class "Default")
      (node (ref "R19") (pin "2") (pinfunction "2_2") (pintype "passive"))
      (node (ref "U2") (pin "6") (pinfunction "ISENA_6") (pintype "passive"))
    )
    (net (code "60") (name "Net-(U2-ISENB)") (class "Default")
      (node (ref "R20") (pin "2") (pinfunction "2_2") (pintype "passive"))
      (node (ref "U2") (pin "9") (pinfunction "ISENB_9") (pintype "passive"))
    )
    (net (code "61") (name "Net-(U2-VCP)") (class "Default")
      (node (ref "C1") (pin "2") (pinfunction "2_2") (pintype "passive"))
      (node (ref "R18") (pin "2") (pinfunction "2_2") (pintype "passive"))
      (node (ref "U2") (pin "3") (pinfunction "VCP_3") (pintype "passive"))
    )
    (net (code "62") (name "Net-(U2-nRESET)") (class "Default")
      (node (ref "R22") (pin "1") (pinfunction "1_1") (pintype "passive"))
      (node (ref "U2") (pin "16") (pinfunction "nRESET_16") (pintype "passive"))
      (node (ref "U2") (pin "17") (pinfunction "nSLEEP_17") (pintype "passive"))
    )
    (net (code "63") (name "Net-(U3-Dir)") (class "Default")
      (node (ref "R23") (pin "1") (pinfunction "1_1") (pintype "passive"))
      (node (ref "U3") (pin "2") (pinfunction "Dir_2") (pintype "passive"))
    )
    (net (code "64") (name "Net-(U3-~{OE})") (class "Default")
      (node (ref "R24") (pin "2") (pinfunction "2_2") (pintype "passive"))
      (node (ref "U3") (pin "22") (pinfunction "~{OE}_22") (pintype "passive"))
    )
    (net (code "65") (name "Net-(U4-AVREF)") (class "Default")
      (node (ref "C14") (pin "1") (pinfunction "1_1") (pintype "passive"))
      (node (ref "U4") (pin "12") (pinfunction "AVREF_12") (pintype "passive"))
      (node (ref "U4") (pin "13") (pinfunction "BVREF_13") (pintype "passive"))
      (node (ref "U4") (pin "15") (pinfunction "V3P3OUT_15") (pintype "passive"))
    )
    (net (code "66") (name "Net-(U4-CP1)") (class "Default")
      (node (ref "C10") (pin "2") (pinfunction "2_2") (pintype "passive"))
      (node (ref "U4") (pin "1") (pinfunction "CP1_1") (pintype "passive"))
    )
    (net (code "67") (name "Net-(U4-CP2)") (class "Default")
      (node (ref "C10") (pin "1") (pinfunction "1_1") (pintype "passive"))
      (node (ref "U4") (pin "2") (pinfunction "CP2_2") (pintype "passive"))
    )
    (net (code "68") (name "Net-(U4-ISENA)") (class "Default")
      (node (ref "R27") (pin "2") (pinfunction "2_2") (pintype "passive"))
      (node (ref "U4") (pin "6") (pinfunction "ISENA_6") (pintype "passive"))
    )
    (net (code "69") (name "Net-(U4-ISENB)") (class "Default")
      (node (ref "R29") (pin "2") (pinfunction "2_2") (pintype "passive"))
      (node (ref "U4") (pin "9") (pinfunction "ISENB_9") (pintype "passive"))
    )
    (net (code "70") (name "Net-(U4-MODE0)") (class "Default")
      (node (ref "R26") (pin "1") (pinfunction "1_1") (pintype "passive"))
      (node (ref "U4") (pin "24") (pinfunction "MODE0_24") (pintype "passive"))
      (node (ref "U4") (pin "25") (pinfunction "MODE1_25") (pintype "passive"))
    )
    (net (code "71") (name "Net-(U4-VCP)") (class "Default")
      (node (ref "C9") (pin "2") (pinfunction "2_2") (pintype "passive"))
      (node (ref "R25") (pin "2") (pinfunction "2_2") (pintype "passive"))
      (node (ref "U4") (pin "3") (pinfunction "VCP_3") (pintype "passive"))
    )
    (net (code "72") (name "Net-(U4-nRESET)") (class "Default")
      (node (ref "R30") (pin "1") (pinfunction "1_1") (pintype "passive"))
      (node (ref "U4") (pin "16") (pinfunction "nRESET_16") (pintype "passive"))
      (node (ref "U4") (pin "17") (pinfunction "nSLEEP_17") (pintype "passive"))
    )
    (net (code "73") (name "Net-(U5-ADecay)") (class "Default")
      (node (ref "R33") (pin "1") (pinfunction "1_1") (pintype "passive"))
      (node (ref "U5") (pin "3") (pinfunction "ADecay_3") (pintype "passive"))
    )
    (net (code "74") (name "Net-(U5-AISEN)") (class "Default")
      (node (ref "R34") (pin "1") (pinfunction "1_1") (pintype "passive"))
      (node (ref "U5") (pin "5") (pinfunction "AISEN_5") (pintype "passive"))
    )
    (net (code "75") (name "Net-(U5-AVREF)") (class "Default")
      (node (ref "U5") (pin "22") (pinfunction "AVREF_22") (pintype "passive"))
      (node (ref "U5") (pin "23") (pinfunction "BVREF_23") (pintype "passive"))
      (node (ref "U5") (pin "24") (pinfunction "VREFO_24") (pintype "passive"))
    )
    (net (code "76") (name "Net-(U5-BDecay)") (class "Default")
      (node (ref "R32") (pin "1") (pinfunction "1_1") (pintype "passive"))
      (node (ref "U5") (pin "2") (pinfunction "BDecay_2") (pintype "passive"))
    )
    (net (code "77") (name "Net-(U5-BISEN)") (class "Default")
      (node (ref "R35") (pin "1") (pinfunction "1_1") (pintype "passive"))
      (node (ref "U5") (pin "8") (pinfunction "BISEN_8") (pintype "passive"))
    )
    (net (code "78") (name "Net-(U5-CONFIG)") (class "Default")
      (node (ref "C15") (pin "2") (pinfunction "2_2") (pintype "passive"))
      (node (ref "U5") (pin "15") (pinfunction "CONFIG_15") (pintype "passive"))
      (node (ref "U5") (pin "20") (pinfunction "VINT_20") (pintype "passive"))
    )
    (net (code "79") (name "Net-(U5-M1)") (class "Default")
      (node (ref "R37") (pin "2") (pinfunction "2_2") (pintype "passive"))
      (node (ref "U5") (pin "14") (pinfunction "M1_14") (pintype "passive"))
    )
    (net (code "80") (name "Net-(U5-VCP)") (class "Default")
      (node (ref "C16") (pin "2") (pinfunction "2_2") (pintype "passive"))
      (node (ref "U5") (pin "17") (pinfunction "VCP_17") (pintype "passive"))
    )
    (net (code "81") (name "Net-(U5-nSleep)") (class "Default")
      (node (ref "R31") (pin "1") (pinfunction "1_1") (pintype "passive"))
      (node (ref "U5") (pin "1") (pinfunction "nSleep_1") (pintype "passive"))
    )
    (net (code "82") (name "Net-(U6-ADecay)") (class "Default")
      (node (ref "R42") (pin "1") (pinfunction "1_1") (pintype "passive"))
      (node (ref "U6") (pin "3") (pinfunction "ADecay_3") (pintype "passive"))
    )
    (net (code "83") (name "Net-(U6-AISEN)") (class "Default")
      (node (ref "R44") (pin "1") (pinfunction "1_1") (pintype "passive"))
      (node (ref "U6") (pin "5") (pinfunction "AISEN_5") (pintype "passive"))
    )
    (net (code "84") (name "Net-(U6-AVREF)") (class "Default")
      (node (ref "U6") (pin "22") (pinfunction "AVREF_22") (pintype "passive"))
      (node (ref "U6") (pin "23") (pinfunction "BVREF_23") (pintype "passive"))
      (node (ref "U6") (pin "24") (pinfunction "VREFO_24") (pintype "passive"))
    )
    (net (code "85") (name "Net-(U6-BDecay)") (class "Default")
      (node (ref "R41") (pin "1") (pinfunction "1_1") (pintype "passive"))
      (node (ref "U6") (pin "2") (pinfunction "BDecay_2") (pintype "passive"))
    )
    (net (code "86") (name "Net-(U6-BISEN)") (class "Default")
      (node (ref "R46") (pin "1") (pinfunction "1_1") (pintype "passive"))
      (node (ref "U6") (pin "8") (pinfunction "BISEN_8") (pintype "passive"))
    )
    (net (code "87") (name "Net-(U6-CONFIG)") (class "Default")
      (node (ref "C17") (pin "2") (pinfunction "2_2") (pintype "passive"))
      (node (ref "U6") (pin "15") (pinfunction "CONFIG_15") (pintype "passive"))
      (node (ref "U6") (pin "20") (pinfunction "VINT_20") (pintype "passive"))
    )
    (net (code "88") (name "Net-(U6-M1)") (class "Default")
      (node (ref "R49") (pin "2") (pinfunction "2_2") (pintype "passive"))
      (node (ref "U6") (pin "14") (pinfunction "M1_14") (pintype "passive"))
    )
    (net (code "89") (name "Net-(U6-VCP)") (class "Default")
      (node (ref "C18") (pin "2") (pinfunction "2_2") (pintype "passive"))
      (node (ref "U6") (pin "17") (pinfunction "VCP_17") (pintype "passive"))
    )
    (net (code "90") (name "Net-(U6-nSleep)") (class "Default")
      (node (ref "R40") (pin "1") (pinfunction "1_1") (pintype "passive"))
      (node (ref "U6") (pin "1") (pinfunction "nSleep_1") (pintype "passive"))
    )
    (net (code "91") (name "Net-(U7-ADecay)") (class "Default")
      (node (ref "R53") (pin "1") (pinfunction "1_1") (pintype "passive"))
      (node (ref "U7") (pin "3") (pinfunction "ADecay_3") (pintype "passive"))
    )
    (net (code "92") (name "Net-(U7-AISEN)") (class "Default")
      (node (ref "R54") (pin "1") (pinfunction "1_1") (pintype "passive"))
      (node (ref "U7") (pin "5") (pinfunction "AISEN_5") (pintype "passive"))
    )
    (net (code "93") (name "Net-(U7-AVREF)") (class "Default")
      (node (ref "U7") (pin "22") (pinfunction "AVREF_22") (pintype "passive"))
      (node (ref "U7") (pin "23") (pinfunction "BVREF_23") (pintype "passive"))
      (node (ref "U7") (pin "24") (pinfunction "VREFO_24") (pintype "passive"))
    )
    (net (code "94") (name "Net-(U7-BDecay)") (class "Default")
      (node (ref "R52") (pin "1") (pinfunction "1_1") (pintype "passive"))
      (node (ref "U7") (pin "2") (pinfunction "BDecay_2") (pintype "passive"))
    )
    (net (code "95") (name "Net-(U7-BISEN)") (class "Default")
      (node (ref "R55") (pin "1") (pinfunction "1_1") (pintype "passive"))
      (node (ref "U7") (pin "8") (pinfunction "BISEN_8") (pintype "passive"))
    )
    (net (code "96") (name "Net-(U7-CONFIG)") (class "Default")
      (node (ref "C19") (pin "2") (pinfunction "2_2") (pintype "passive"))
      (node (ref "U7") (pin "15") (pinfunction "CONFIG_15") (pintype "passive"))
      (node (ref "U7") (pin "20") (pinfunction "VINT_20") (pintype "passive"))
    )
    (net (code "97") (name "Net-(U7-M1)") (class "Default")
      (node (ref "R57") (pin "2") (pinfunction "2_2") (pintype "passive"))
      (node (ref "U7") (pin "14") (pinfunction "M1_14") (pintype "passive"))
    )
    (net (code "98") (name "Net-(U7-VCP)") (class "Default")
      (node (ref "C20") (pin "2") (pinfunction "2_2") (pintype "passive"))
      (node (ref "U7") (pin "17") (pinfunction "VCP_17") (pintype "passive"))
    )
    (net (code "99") (name "Net-(U7-nSleep)") (class "Default")
      (node (ref "R51") (pin "1") (pinfunction "1_1") (pintype "passive"))
      (node (ref "U7") (pin "1") (pinfunction "nSleep_1") (pintype "passive"))
    )
    (net (code "100") (name "VCC_3V3") (class "Default")
      (node (ref "C8") (pin "1") (pinfunction "1_1") (pintype "passive"))
      (node (ref "R22") (pin "2") (pinfunction "2_2") (pintype "passive"))
      (node (ref "R26") (pin "2") (pinfunction "2_2") (pintype "passive"))
      (node (ref "R30") (pin "2") (pinfunction "2_2") (pintype "passive"))
      (node (ref "U3") (pin "23") (pinfunction "VCCB(3.3V)_23") (pintype "passive"))
      (node (ref "U3") (pin "24") (pinfunction "VCCB(3.3V)_24") (pintype "passive"))
    )
    (net (code "101") (name "VCC_5V") (class "Default")
      (node (ref "C16") (pin "1") (pinfunction "1_1") (pintype "passive"))
      (node (ref "C18") (pin "1") (pinfunction "1_1") (pintype "passive"))
      (node (ref "C20") (pin "1") (pinfunction "1_1") (pintype "passive"))
      (node (ref "C7") (pin "2") (pinfunction "2_2") (pintype "passive"))
      (node (ref "PH2") (pin "1") (pinfunction "1_1") (pintype "passive"))
      (node (ref "PH3") (pin "1") (pinfunction "1_1") (pintype "passive"))
      (node (ref "PH5") (pin "1") (pinfunction "1_1") (pintype "passive"))
      (node (ref "PH7") (pin "1") (pinfunction "1_1") (pintype "passive"))
      (node (ref "PH8") (pin "1") (pinfunction "1_1") (pintype "passive"))
      (node (ref "Q6") (pin "1") (pinfunction "E_1") (pintype "passive"))
      (node (ref "R21") (pin "2") (pinfunction "2_2") (pintype "passive"))
      (node (ref "R23") (pin "2") (pinfunction "2_2") (pintype "passive"))
      (node (ref "R28") (pin "2") (pinfunction "2_2") (pintype "passive"))
      (node (ref "R31") (pin "2") (pinfunction "2_2") (pintype "passive"))
      (node (ref "R36") (pin "2") (pinfunction "2_2") (pintype "passive"))
      (node (ref "R37") (pin "1") (pinfunction "1_1") (pintype "passive"))
      (node (ref "R39") (pin "2") (pinfunction "2_2") (pintype "passive"))
      (node (ref "R40") (pin "2") (pinfunction "2_2") (pintype "passive"))
      (node (ref "R43") (pin "2") (pinfunction "2_2") (pintype "passive"))
      (node (ref "R47") (pin "2") (pinfunction "2_2") (pintype "passive"))
      (node (ref "R49") (pin "1") (pinfunction "1_1") (pintype "passive"))
      (node (ref "R51") (pin "2") (pinfunction "2_2") (pintype "passive"))
      (node (ref "R56") (pin "1") (pinfunction "1_1") (pintype "passive"))
      (node (ref "R57") (pin "1") (pinfunction "1_1") (pintype "passive"))
      (node (ref "U3") (pin "1") (pinfunction "Vcc(5V)_1") (pintype "passive"))
      (node (ref "U5") (pin "18") (pinfunction "VM_18") (pintype "passive"))
      (node (ref "U5") (pin "19") (pinfunction "VM_19") (pintype "passive"))
      (node (ref "U6") (pin "18") (pinfunction "VM_18") (pintype "passive"))
      (node (ref "U6") (pin "19") (pinfunction "VM_19") (pintype "passive"))
      (node (ref "U7") (pin "18") (pinfunction "VM_18") (pintype "passive"))
      (node (ref "U7") (pin "19") (pinfunction "VM_19") (pintype "passive"))
    )
    (net (code "102") (name "VCC_12V") (class "Default")
      (node (ref "R38") (pin "1") (pinfunction "1_1") (pintype "passive"))
    )
    (net (code "103") (name "VCC_24V") (class "Default")
      (node (ref "C1") (pin "1") (pinfunction "1_1") (pintype "passive"))
      (node (ref "C11") (pin "2") (pinfunction "2_2") (pintype "passive"))
      (node (ref "C12") (pin "2") (pinfunction "2_2") (pintype "passive"))
      (node (ref "C13") (pin "2") (pinfunction "2_2") (pintype "passive"))
      (node (ref "C3") (pin "2") (pinfunction "2_2") (pintype "passive"))
      (node (ref "C4") (pin "2") (pinfunction "2_2") (pintype "passive"))
      (node (ref "C5") (pin "2") (pinfunction "2_2") (pintype "passive"))
      (node (ref "C9") (pin "1") (pinfunction "1_1") (pintype "passive"))
      (node (ref "R18") (pin "1") (pinfunction "1_1") (pintype "passive"))
      (node (ref "R25") (pin "1") (pinfunction "1_1") (pintype "passive"))
      (node (ref "U2") (pin "11") (pinfunction "VMB_11") (pintype "passive"))
      (node (ref "U2") (pin "4") (pinfunction "VMA_4") (pintype "passive"))
      (node (ref "U4") (pin "11") (pinfunction "VMB_11") (pintype "passive"))
      (node (ref "U4") (pin "4") (pinfunction "VMA_4") (pintype "passive"))
    )
    (net (code "104") (name "unconnected-(U2-DECAY-Pad19)") (class "Default")
      (node (ref "U2") (pin "19") (pinfunction "DECAY_19") (pintype "passive+no_connect"))
    )
    (net (code "105") (name "unconnected-(U2-NC-Pad23)") (class "Default")
      (node (ref "U2") (pin "23") (pinfunction "NC_23") (pintype "passive+no_connect"))
    )
    (net (code "106") (name "unconnected-(U2-nFAULT-Pad18)") (class "Default")
      (node (ref "U2") (pin "18") (pinfunction "nFAULT_18") (pintype "passive+no_connect"))
    )
    (net (code "107") (name "unconnected-(U2-nHOME-Pad27)") (class "Default")
      (node (ref "U2") (pin "27") (pinfunction "nHOME_27") (pintype "passive+no_connect"))
    )
    (net (code "108") (name "unconnected-(U3-A1-Pad3)") (class "Default")
      (node (ref "U3") (pin "3") (pinfunction "A1_3") (pintype "passive+no_connect"))
    )
    (net (code "109") (name "unconnected-(U3-A7-Pad9)") (class "Default")
      (node (ref "U3") (pin "9") (pinfunction "A7_9") (pintype "passive+no_connect"))
    )
    (net (code "110") (name "unconnected-(U3-A8-Pad10)") (class "Default")
      (node (ref "U3") (pin "10") (pinfunction "A8_10") (pintype "passive+no_connect"))
    )
    (net (code "111") (name "unconnected-(U3-B1-Pad21)") (class "Default")
      (node (ref "U3") (pin "21") (pinfunction "B1_21") (pintype "passive+no_connect"))
    )
    (net (code "112") (name "unconnected-(U3-B7-Pad15)") (class "Default")
      (node (ref "U3") (pin "15") (pinfunction "B7_15") (pintype "passive+no_connect"))
    )
    (net (code "113") (name "unconnected-(U3-B8-Pad14)") (class "Default")
      (node (ref "U3") (pin "14") (pinfunction "B8_14") (pintype "passive+no_connect"))
    )
    (net (code "114") (name "unconnected-(U4-DECAY-Pad19)") (class "Default")
      (node (ref "U4") (pin "19") (pinfunction "DECAY_19") (pintype "passive+no_connect"))
    )
    (net (code "115") (name "unconnected-(U4-NC-Pad23)") (class "Default")
      (node (ref "U4") (pin "23") (pinfunction "NC_23") (pintype "passive+no_connect"))
    )
    (net (code "116") (name "unconnected-(U4-nFAULT-Pad18)") (class "Default")
      (node (ref "U4") (pin "18") (pinfunction "nFAULT_18") (pintype "passive+no_connect"))
    )
    (net (code "117") (name "unconnected-(U4-nHOME-Pad27)") (class "Default")
      (node (ref "U4") (pin "27") (pinfunction "nHOME_27") (pintype "passive+no_connect"))
    )
    (net (code "118") (name "unconnected-(U5-nFAULT-Pad16)") (class "Default")
      (node (ref "U5") (pin "16") (pinfunction "nFAULT_16") (pintype "passive+no_connect"))
    )
    (net (code "119") (name "unconnected-(U6-nFAULT-Pad16)") (class "Default")
      (node (ref "U6") (pin "16") (pinfunction "nFAULT_16") (pintype "passive+no_connect"))
    )
    (net (code "120") (name "unconnected-(U7-nFAULT-Pad16)") (class "Default")
      (node (ref "U7") (pin "16") (pinfunction "nFAULT_16") (pintype "passive+no_connect"))
    )
  )
)
